# Eurorack_Pot_CV_Summed.net
KiCad netlist of a schematic drawn in EAGLE
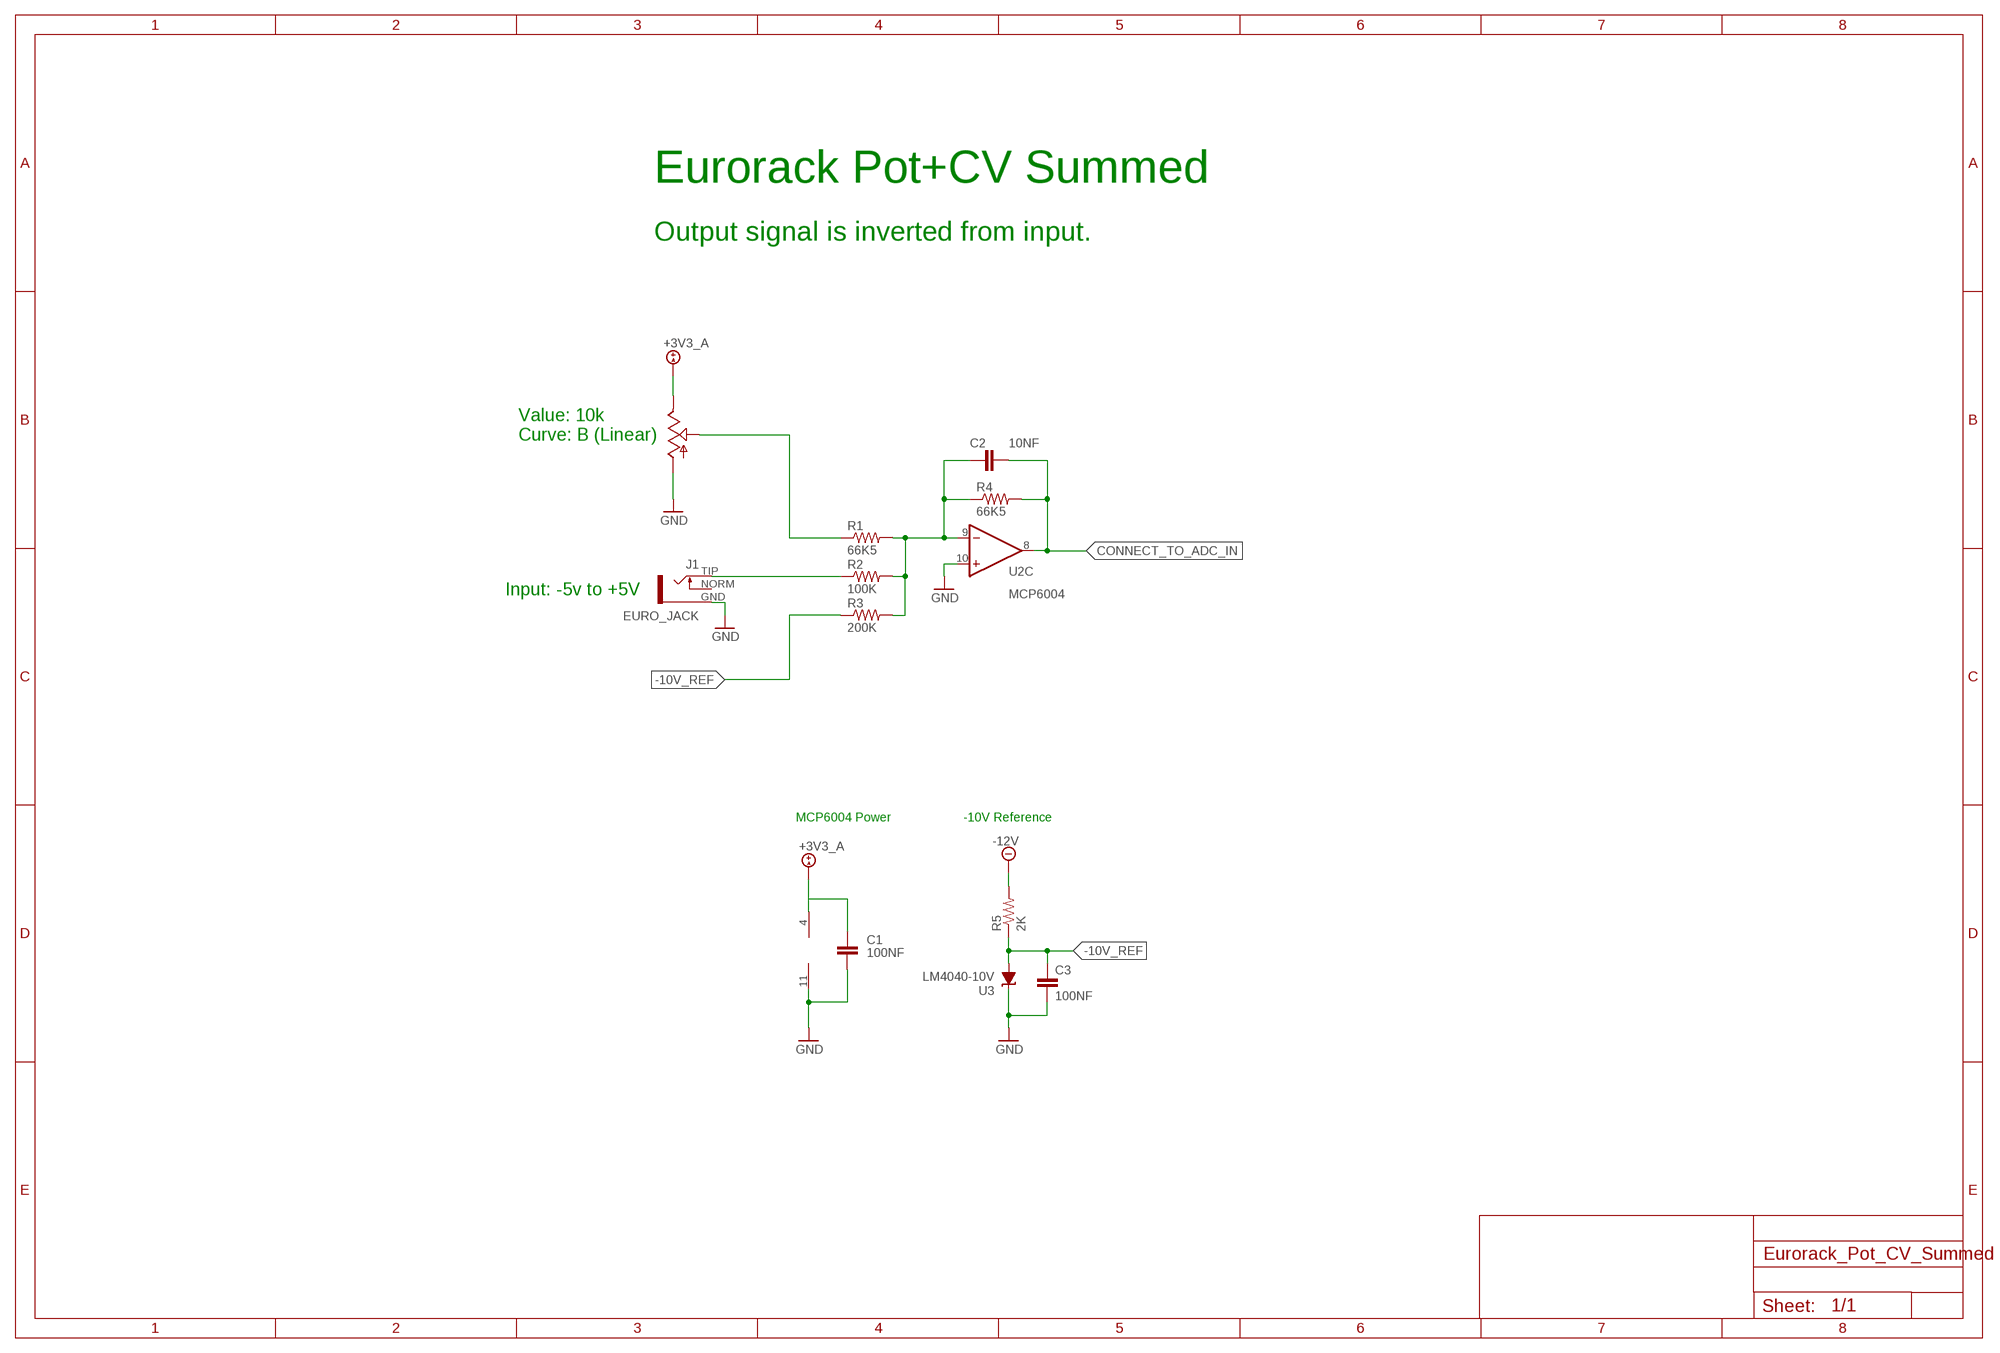
[diagram p0: schematic, sheet 1]

(export (version "E")
  (design (tool "Eeschema 10.0.6"))
  (components
    (comp (ref "C1")
      (value "100NF")
      (footprint "eagle-import:C0603")
      (libsource (lib "eagle-import") (part "C-EUC0603"))
    )
    (comp (ref "C2")
      (value "10NF")
      (footprint "eagle-import:C0603")
      (libsource (lib "eagle-import") (part "C-EUC0603"))
    )
    (comp (ref "C3")
      (value "100NF")
      (footprint "eagle-import:C0603")
      (libsource (lib "eagle-import") (part "C-EUC0603"))
    )
    (comp (ref "J1")
      (value "EURO_JACK")
      (footprint "eagle-import:S_JACK")
      (libsource (lib "eagle-import") (part "EURO_JACK"))
    )
    (comp (ref "R1")
      (value "66K5")
      (footprint "eagle-import:R0603")
      (libsource (lib "eagle-import") (part "R-US_R0603"))
    )
    (comp (ref "R2")
      (value "100K")
      (footprint "eagle-import:R0603")
      (libsource (lib "eagle-import") (part "R-US_R0603"))
    )
    (comp (ref "R3")
      (value "200K")
      (footprint "eagle-import:R0603")
      (libsource (lib "eagle-import") (part "R-US_R0603"))
    )
    (comp (ref "R4")
      (value "66K5")
      (footprint "eagle-import:R0603")
      (libsource (lib "eagle-import") (part "R-US_R0603"))
    )
    (comp (ref "R5")
      (value "2K")
      (footprint "eagle-import:R0603")
      (libsource (lib "eagle-import") (part "R-US_R0603"))
    )
    (comp (ref "U1")
      (value "MCP6004")
      (footprint "eagle-import:TSSOP-14")
      (fields (field (name "MPN") "MCP6004T-E/ST"))
      (libsource (lib "eagle-import") (part "MCP6004_TSSOP-14"))
    )
    (comp (ref "U2")
      (value "MCP6004")
      (footprint "eagle-import:TSSOP-14")
      (fields (field (name "MPN") "MCP6004T-E/ST"))
      (libsource (lib "eagle-import") (part "MCP6004_TSSOP-14"))
    )
    (comp (ref "U3")
      (value "LM4040-10V")
      (footprint "eagle-import:DBZ_R-PDSO-G3")
      (fields (field (name "MPN") "LM4041A12IDBZR"))
      (libsource (lib "eagle-import") (part "LM4040-10VDBZA12"))
    )
    (comp (ref "VR1")
      (value "POT_9MM_SNAP-IN__")
      (footprint "eagle-import:9MM_SNAP-IN_POT_SILK")
      (libsource (lib "eagle-import") (part "POT_9MM_SNAP-IN__"))
    )
  )
  (nets
    (net (code "1") (name "+3V3_A") (class "Default")
      (node (ref "C1") (pin "2") (pinfunction "2_2") (pintype "passive"))
      (node (ref "U1") (pin "4") (pinfunction "V+_4") (pintype "power_in"))
      (node (ref "VR1") (pin "3") (pinfunction "3_3") (pintype "passive"))
    )
    (net (code "2") (name "-10V_REF") (class "Default")
      (node (ref "C3") (pin "1") (pinfunction "1_1") (pintype "passive"))
      (node (ref "R3") (pin "1") (pinfunction "1_1") (pintype "passive"))
      (node (ref "R5") (pin "1") (pinfunction "1_1") (pintype "passive"))
      (node (ref "U3") (pin "2") (pinfunction "A_2") (pintype "passive"))
    )
    (net (code "3") (name "-12V") (class "Default")
      (node (ref "R5") (pin "2") (pinfunction "2_2") (pintype "passive"))
    )
    (net (code "4") (name "CONNECT_TO_ADC_IN") (class "Default")
      (node (ref "C2") (pin "2") (pinfunction "2_2") (pintype "passive"))
      (node (ref "R4") (pin "2") (pinfunction "2_2") (pintype "passive"))
      (node (ref "U2") (pin "8") (pinfunction "OUT_8") (pintype "output"))
    )
    (net (code "5") (name "GND") (class "Default")
      (node (ref "C1") (pin "1") (pinfunction "1_1") (pintype "passive"))
      (node (ref "C3") (pin "2") (pinfunction "2_2") (pintype "passive"))
      (node (ref "J1") (pin "GND") (pinfunction "GND_GND") (pintype "passive"))
      (node (ref "U1") (pin "11") (pinfunction "V-_11") (pintype "power_in"))
      (node (ref "U2") (pin "10") (pinfunction "+IN_10") (pintype "input"))
      (node (ref "U3") (pin "1") (pinfunction "C_1") (pintype "passive"))
      (node (ref "VR1") (pin "1") (pinfunction "1_1") (pintype "passive"))
    )
    (net (code "6") (name "Net-(J1-PadTIP)") (class "Default")
      (node (ref "J1") (pin "TIP") (pinfunction "TIP_TIP") (pintype "passive"))
      (node (ref "R2") (pin "1") (pinfunction "1_1") (pintype "passive"))
    )
    (net (code "7") (name "Net-(R1-Pad1)") (class "Default")
      (node (ref "R1") (pin "1") (pinfunction "1_1") (pintype "passive"))
      (node (ref "VR1") (pin "2") (pinfunction "2_2") (pintype "passive"))
    )
    (net (code "8") (name "Net-(U2C--IN)") (class "Default")
      (node (ref "C2") (pin "1") (pinfunction "1_1") (pintype "passive"))
      (node (ref "R1") (pin "2") (pinfunction "2_2") (pintype "passive"))
      (node (ref "R2") (pin "2") (pinfunction "2_2") (pintype "passive"))
      (node (ref "R3") (pin "2") (pinfunction "2_2") (pintype "passive"))
      (node (ref "R4") (pin "1") (pinfunction "1_1") (pintype "passive"))
      (node (ref "U2") (pin "9") (pinfunction "-IN_9") (pintype "input"))
    )
    (net (code "9") (name "unconnected-(J1-PadNORM)") (class "Default")
      (node (ref "J1") (pin "NORM") (pinfunction "NORM_NORM") (pintype "passive"))
    )
  )
)
